# Line_Detector.net
KiCad netlist of a schematic drawn in EAGLE
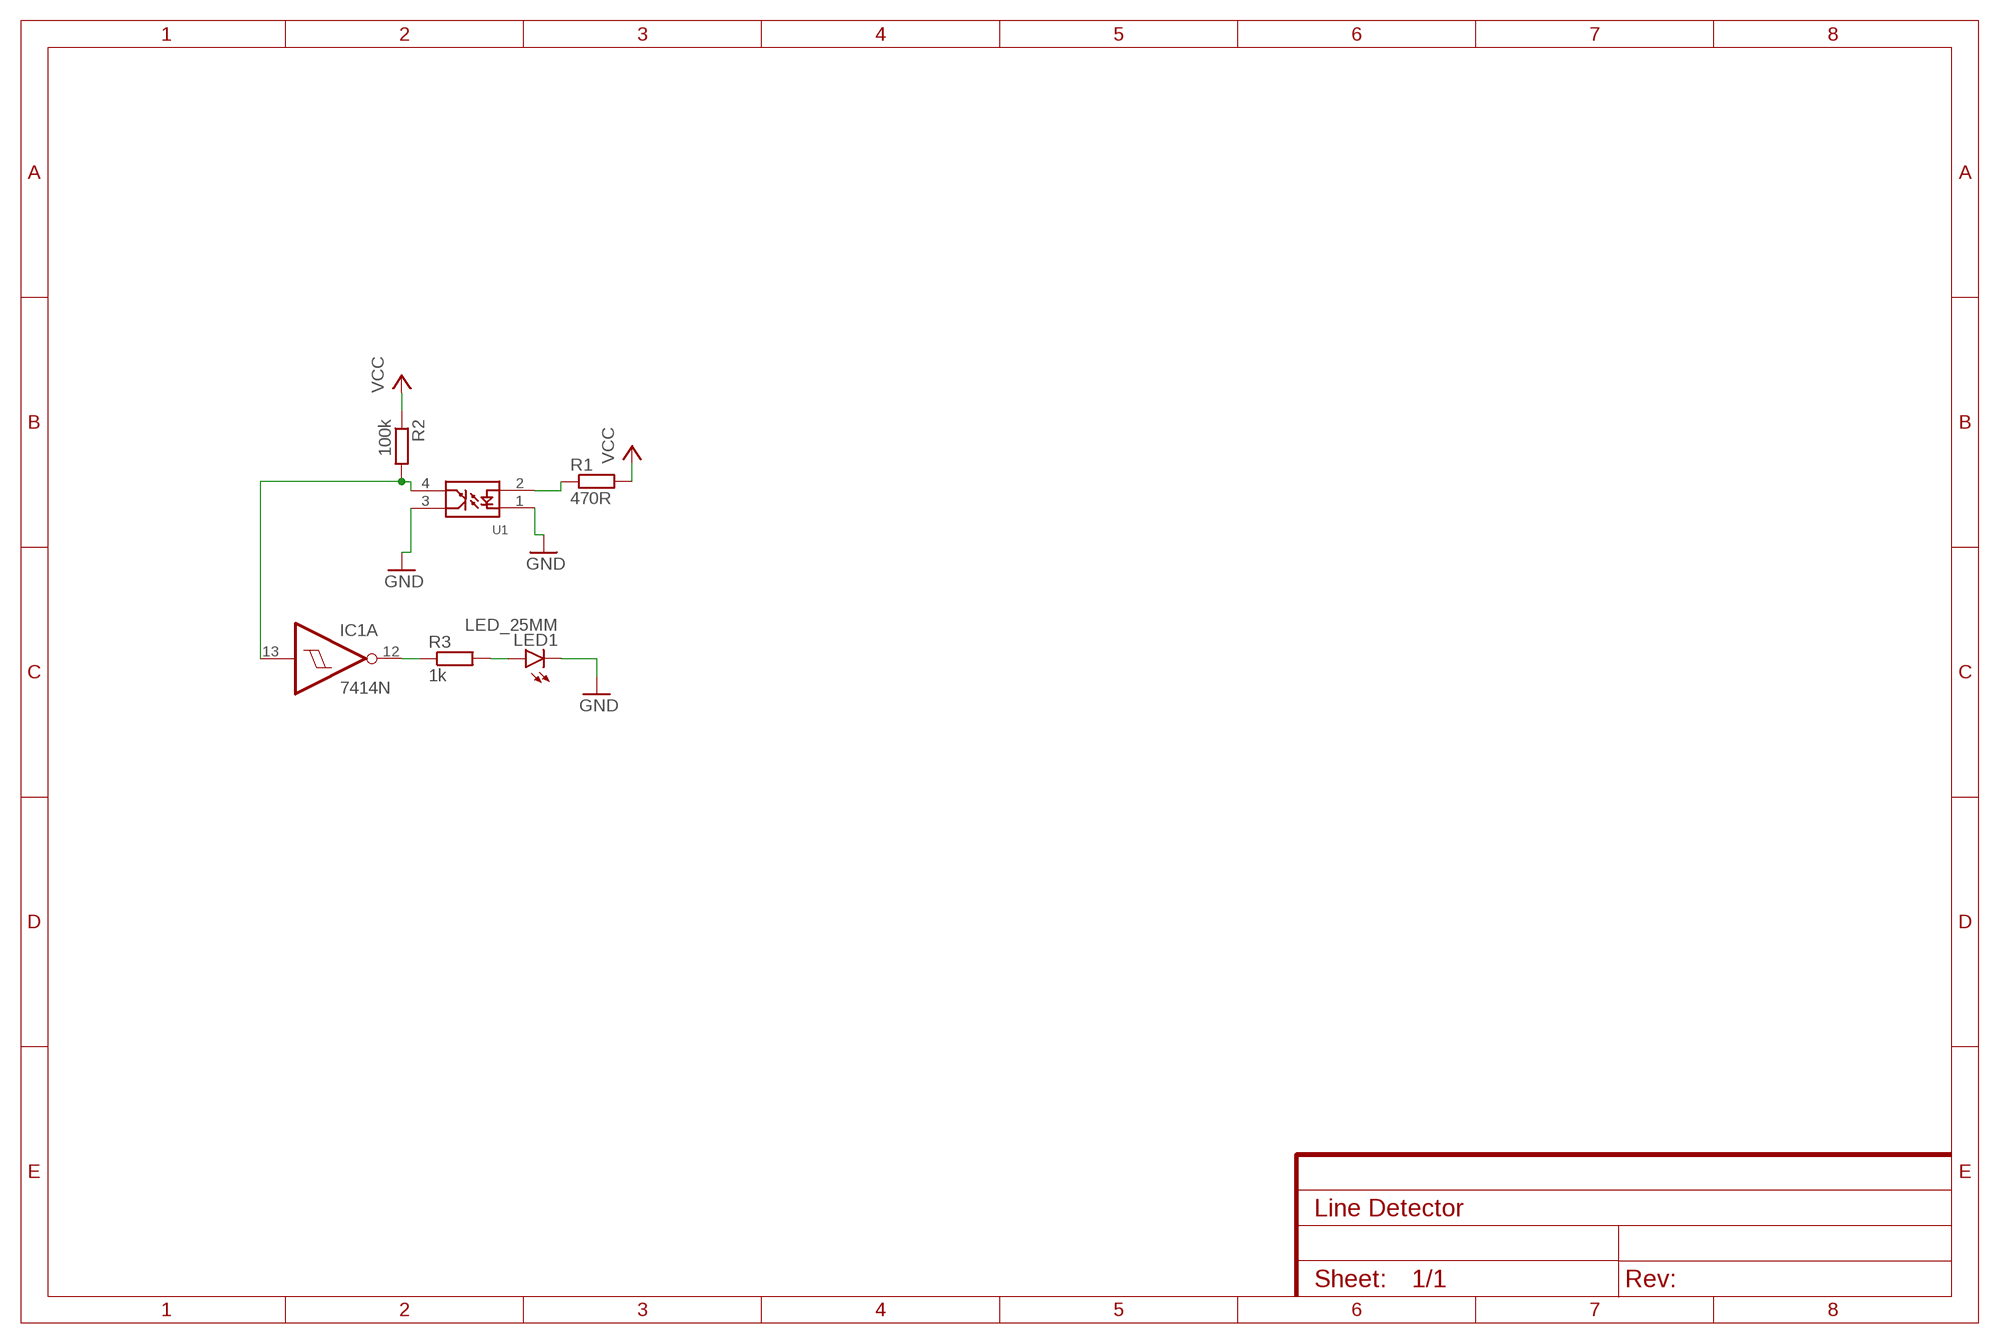
[diagram p0: schematic, sheet 1]

(export (version "E")
  (design (tool "Eeschema 10.0.6"))
  (components
    (comp (ref "IC1")
      (value "7414N")
      (footprint "eagle-import:DIL14")
      (libsource (lib "eagle-import") (part "7414N"))
    )
    (comp (ref "LED1")
      (value "LED_25MM")
      (footprint "eagle-import:LED5MM")
      (libsource (lib "eagle-import") (part "LED_25MM"))
    )
    (comp (ref "R1")
      (value "470R")
      (footprint "eagle-import:0204_7")
      (libsource (lib "eagle-import") (part "R-EU_0204/7"))
    )
    (comp (ref "R2")
      (value "100k")
      (footprint "eagle-import:0204_7")
      (libsource (lib "eagle-import") (part "R-EU_0204/7"))
    )
    (comp (ref "R3")
      (value "1k")
      (footprint "eagle-import:0204_7")
      (libsource (lib "eagle-import") (part "R-EU_0204/7"))
    )
    (comp (ref "U1")
      (value "OPB704")
      (footprint "eagle-import:22-23-2041")
      (libsource (lib "eagle-import") (part "OPB704"))
    )
  )
  (nets
    (net (code "1") (name "GND") (class "Default")
      (node (ref "LED1") (pin "K") (pinfunction "C_K") (pintype "passive"))
      (node (ref "U1") (pin "1") (pinfunction "1_1") (pintype "bidirectional"))
      (node (ref "U1") (pin "3") (pinfunction "3_3") (pintype "bidirectional"))
    )
    (net (code "2") (name "Net-(IC1A-I)") (class "Default")
      (node (ref "IC1") (pin "13") (pinfunction "I_13") (pintype "input"))
      (node (ref "R2") (pin "2") (pinfunction "2_2") (pintype "passive"))
      (node (ref "U1") (pin "4") (pinfunction "4_4") (pintype "bidirectional"))
    )
    (net (code "3") (name "Net-(IC1A-O)") (class "Default")
      (node (ref "IC1") (pin "12") (pinfunction "O_12") (pintype "output"))
      (node (ref "R3") (pin "1") (pinfunction "1_1") (pintype "passive"))
    )
    (net (code "4") (name "Net-(LED1-PadA)") (class "Default")
      (node (ref "LED1") (pin "A") (pinfunction "A_A") (pintype "passive"))
      (node (ref "R3") (pin "2") (pinfunction "2_2") (pintype "passive"))
    )
    (net (code "5") (name "Net-(R1-Pad1)") (class "Default")
      (node (ref "R1") (pin "1") (pinfunction "1_1") (pintype "passive"))
      (node (ref "U1") (pin "2") (pinfunction "2_2") (pintype "bidirectional"))
    )
    (net (code "6") (name "VCC") (class "Default")
      (node (ref "R1") (pin "2") (pinfunction "2_2") (pintype "passive"))
      (node (ref "R2") (pin "1") (pinfunction "1_1") (pintype "passive"))
    )
  )
)
